# 01_Power_Suppy.net
KiCad netlist of a schematic drawn in Altium Designer
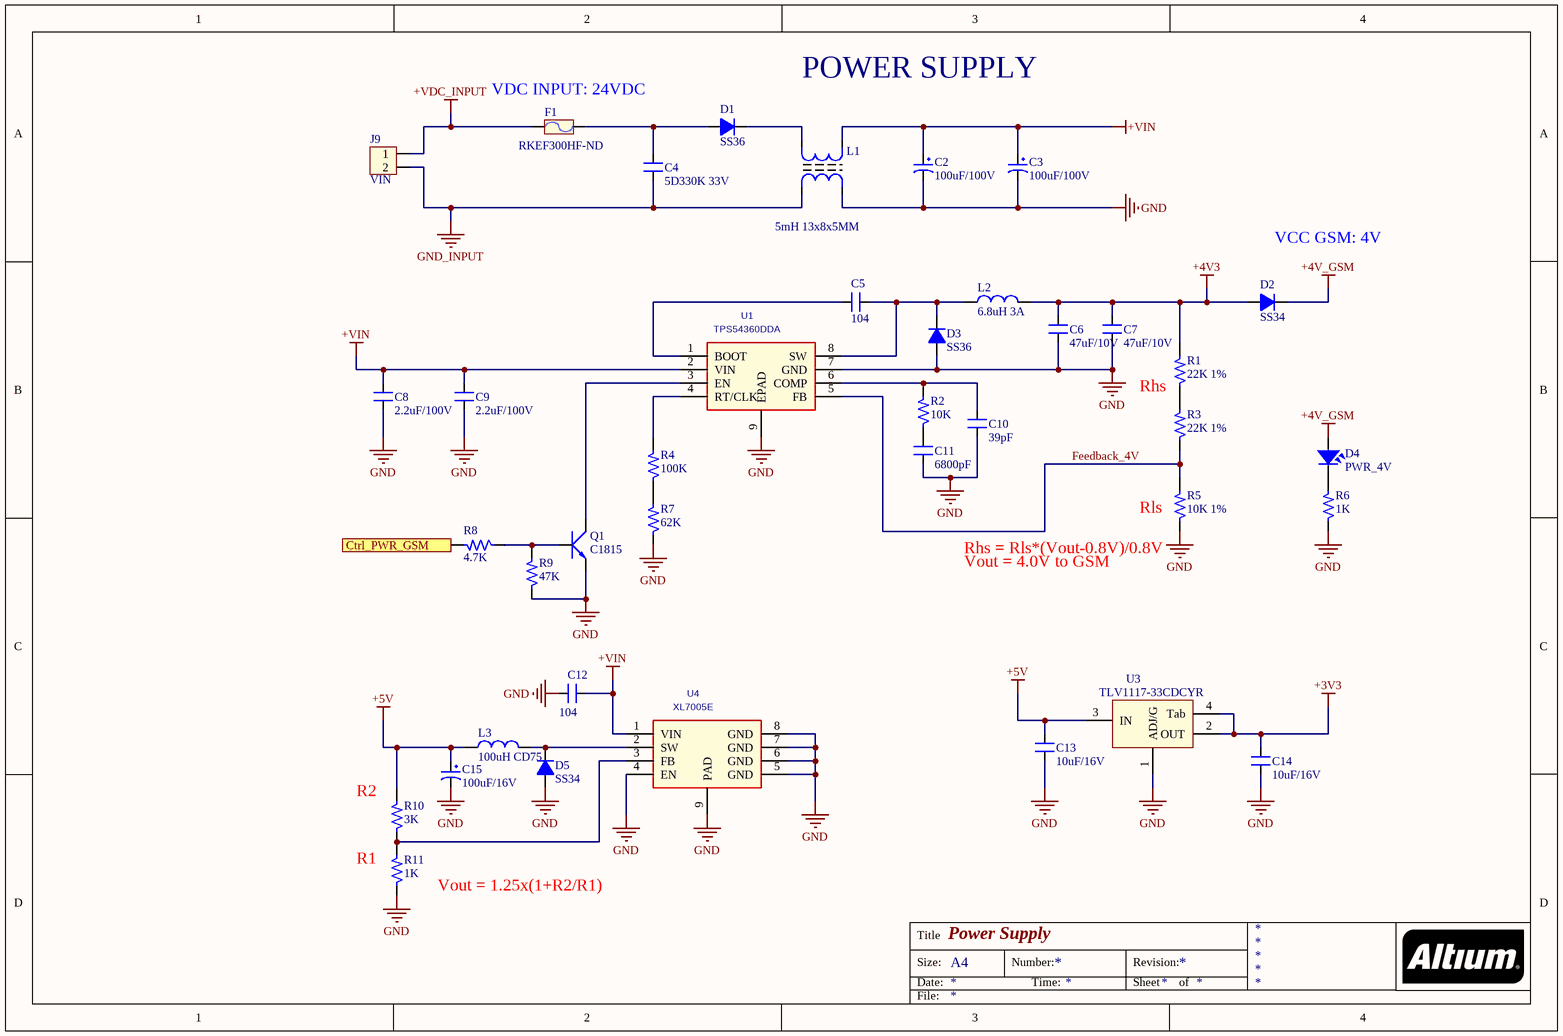
[diagram p0: [01] Power Suppy.SchDoc]

(export (version "E")
  (design (tool "Eeschema 10.0.6"))
  (components
    (comp (ref "C2")
      (value "100uF/100V")
      (footprint "CP1.5/3.4")
      (description "Cap 1000uF/16V - 220uF/50V")
      (libsource (lib "khapham") (part "CP4"))
    )
    (comp (ref "C3")
      (value "100uF/100V")
      (footprint "CP1.5/3.4")
      (description "Cap 1000uF/16V - 220uF/50V")
      (libsource (lib "khapham") (part "CP4"))
    )
    (comp (ref "C4")
      (value "5D330K 33V")
      (footprint "CN2")
      (fields (field (name "DESIGNED BY") "VanDungEvn"))
      (libsource (lib "khapham") (part "CN"))
    )
    (comp (ref "C5")
      (value "104")
      (footprint "C0603 SMT")
      (description "Cap SMD")
      (libsource (lib "khapham") (part "CM"))
    )
    (comp (ref "C6")
      (value "47uF/10V")
      (footprint "SM-1210")
      (description "CAP CER 47UF 10V X5R 1210")
      (libsource (lib "khapham") (part "CM"))
    )
    (comp (ref "C7")
      (value "47uF/10V")
      (footprint "SM-1210")
      (description "CAP CER 47UF 10V X5R 1210 1276-3380-2-ND")
      (libsource (lib "khapham") (part "CM"))
    )
    (comp (ref "C8")
      (value "2.2uF/100V")
      (footprint "SM-1210")
      (description "CAP CER 2.2UF 100V X7R 1210  445-4498-2-ND")
      (libsource (lib "khapham") (part "CM"))
    )
    (comp (ref "C9")
      (value "2.2uF/100V")
      (footprint "SM-1210")
      (description "CAP CER 2.2UF 100V X7R 1210  445-4498-2-ND")
      (libsource (lib "khapham") (part "CM"))
    )
    (comp (ref "C10")
      (value "39pF")
      (footprint "C0603 SMT")
      (description "Cap SMD")
      (libsource (lib "khapham") (part "CM"))
    )
    (comp (ref "C11")
      (value "6800pF")
      (footprint "C0603 SMT")
      (description "Cap SMD")
      (libsource (lib "khapham") (part "CM"))
    )
    (comp (ref "C12")
      (value "104")
      (footprint "C0603 SMT")
      (description "Cap SMD")
      (libsource (lib "khapham") (part "CM"))
    )
    (comp (ref "C13")
      (value "10uF/16V")
      (footprint "C0603 SMT")
      (description "Cap SMD")
      (libsource (lib "khapham") (part "CM"))
    )
    (comp (ref "C14")
      (value "10uF/16V")
      (footprint "C0603 SMT")
      (description "Cap SMD")
      (libsource (lib "khapham") (part "CM"))
    )
    (comp (ref "C15")
      (value "100uF/16V")
      (footprint "C_Alu_6.3x7.7")
      (description "Cap Aluminum, Tantalum 7343")
      (libsource (lib "khapham") (part "C-Alu-Tantalum"))
    )
    (comp (ref "D1")
      (value "SS36")
      (footprint "DO-214AB SMA")
      (description "DIODE SCHOTTKY 60V 3A SMA")
      (libsource (lib "khapham") (part "D5A"))
    )
    (comp (ref "D2")
      (value "SS34")
      (footprint "DO-214AB SMA")
      (description "DIODE SCHOTTKY 40V 3A SMC")
      (libsource (lib "khapham") (part "D1A"))
    )
    (comp (ref "D3")
      (value "SS36")
      (footprint "DO-214AB SMA")
      (description "DIODE SCHOTTKY 60V 3A SMA")
      (libsource (lib "khapham") (part "D5A"))
    )
    (comp (ref "D4")
      (value "PWR_4V")
      (footprint "Led_0603_Green")
      (description "LED 0603 RED")
      (libsource (lib "khapham") (part "LED"))
    )
    (comp (ref "D5")
      (value "SS34")
      (footprint "DO-214AB SMA")
      (description "DIODE SCHOTTKY 40V 3A SMC")
      (libsource (lib "khapham") (part "D1A"))
    )
    (comp (ref "F1")
      (value "RKEF300HF-ND")
      (footprint "FUSE2")
      (description "PTC RESET FUSE 60V 3A RADIAL")
      (fields (field (name "DESIGNED BY") "VanDungEvn"))
      (libsource (lib "khapham") (part "Fuse"))
    )
    (comp (ref "J9")
      (value "VIN")
      (footprint "Hed2V_3.96")
      (description "Header 2 (Green)")
      (libsource (lib "khapham") (part "Hed2"))
    )
    (comp (ref "L1")
      (value "5mH 13x8x5MM")
      (footprint "L2 UF9.8")
      (fields (field (name "DESIGNED BY") "VanDungEvn"))
      (libsource (lib "khapham") (part "L2x220"))
    )
    (comp (ref "L2")
      (value "6.8uH 3A")
      (footprint "L01 SMD 12*12*6")
      (description "6.8uH 3A 12x12x7MM")
      (libsource (lib "khapham") (part "L1"))
    )
    (comp (ref "L3") (value "100uH CD75") (footprint "L01 CD75") (libsource (lib "khapham") (part "L1")))
    (comp (ref "Q1")
      (value "C1815")
      (footprint "SOT23B")
      (description "NPN 600mW, ECB")
      (libsource (lib "khapham") (part "C1815"))
    )
    (comp (ref "R1")
      (value "22K 1%")
      (footprint "R0603 -SMT")
      (description "Resistor SMD")
      (libsource (lib "khapham") (part "RM"))
    )
    (comp (ref "R2")
      (value "10K")
      (footprint "R0603 -SMT")
      (description "Resistor SMD")
      (libsource (lib "khapham") (part "RM"))
    )
    (comp (ref "R3")
      (value "22K 1%")
      (footprint "R0603 -SMT")
      (description "Resistor SMD")
      (libsource (lib "khapham") (part "RM"))
    )
    (comp (ref "R4")
      (value "100K")
      (footprint "R0603 -SMT")
      (description "Resistor SMD")
      (libsource (lib "khapham") (part "RM"))
    )
    (comp (ref "R5")
      (value "10K 1%")
      (footprint "R0603 -SMT")
      (description "Resistor SMD")
      (libsource (lib "khapham") (part "RM"))
    )
    (comp (ref "R6")
      (value "1K")
      (footprint "R0603 -SMT")
      (description "Resistor SMD")
      (libsource (lib "khapham") (part "RM"))
    )
    (comp (ref "R7")
      (value "62K")
      (footprint "R0603 -SMT")
      (description "Resistor SMD")
      (libsource (lib "khapham") (part "RM"))
    )
    (comp (ref "R8")
      (value "4.7K")
      (footprint "R0603 -SMT")
      (description "Resistor SMD")
      (libsource (lib "khapham") (part "RM"))
    )
    (comp (ref "R9")
      (value "47K")
      (footprint "R0603 -SMT")
      (description "Resistor SMD")
      (libsource (lib "khapham") (part "RM"))
    )
    (comp (ref "R10")
      (value "3K")
      (footprint "R0603 -SMT")
      (description "Resistor SMD")
      (libsource (lib "khapham") (part "RM"))
    )
    (comp (ref "R11")
      (value "1K")
      (footprint "R0603 -SMT")
      (description "Resistor SMD")
      (libsource (lib "khapham") (part "RM"))
    )
    (comp (ref "U1")
      (value "TPS54360DDA")
      (footprint "DDA8_3P1X2P4-M")
      (description "REG BUCK SPLIT RAIL 8SOPWRPAD")
      (libsource (lib "khapham") (part "TPS54360DDA"))
    )
    (comp (ref "U3")
      (value "TLV1117-33CDCYR")
      (footprint "SOT223-4N")
      (description "3v3")
      (libsource (lib "khapham") (part "LM1117"))
    )
    (comp (ref "U4")
      (value "XL7005E")
      (footprint "DDA8_3P1X2P4-M")
      (description "REG BUCK SPLIT RAIL 8SOPWRPAD")
      (fields (field (name "MANUFACTURER_PART_NUMBER") "TPS54360DDA"))
      (libsource (lib "khapham") (part "XL7005"))
    )
  )
  (nets
    (net (code "1") (name "+3V3") (class "Default")
      (node (ref "C14") (pin "2") (pinfunction "2_2") (pintype "passive"))
      (node (ref "U3") (pin "2") (pinfunction "OUT_2") (pintype "passive"))
      (node (ref "U3") (pin "4") (pinfunction "Tab_4") (pintype "passive"))
    )
    (net (code "2") (name "+4V3") (class "Default")
      (node (ref "C6") (pin "2") (pinfunction "2_2") (pintype "passive"))
      (node (ref "C7") (pin "2") (pinfunction "2_2") (pintype "passive"))
      (node (ref "D2") (pin "1") (pinfunction "A_1") (pintype "passive"))
      (node (ref "L2") (pin "2") (pinfunction "2_2") (pintype "passive"))
      (node (ref "R1") (pin "2") (pinfunction "2_2") (pintype "passive"))
    )
    (net (code "3") (name "+4V_GSM") (class "Default")
      (node (ref "D2") (pin "2") (pinfunction "K_2") (pintype "passive"))
      (node (ref "D4") (pin "1") (pinfunction "1_1") (pintype "passive"))
    )
    (net (code "4") (name "+5V") (class "Default")
      (node (ref "C13") (pin "2") (pinfunction "2_2") (pintype "passive"))
      (node (ref "C15") (pin "1") (pinfunction "1_1") (pintype "passive"))
      (node (ref "L3") (pin "1") (pinfunction "1_1") (pintype "passive"))
      (node (ref "R10") (pin "2") (pinfunction "2_2") (pintype "passive"))
      (node (ref "U3") (pin "3") (pinfunction "IN_3") (pintype "passive"))
    )
    (net (code "5") (name "+VDC_INPUT") (class "Default")
      (node (ref "F1") (pin "1") (pinfunction "1_1") (pintype "passive"))
      (node (ref "J9") (pin "1") (pinfunction "1_1") (pintype "passive"))
    )
    (net (code "6") (name "+VIN") (class "Default")
      (node (ref "C12") (pin "2") (pinfunction "2_2") (pintype "passive"))
      (node (ref "C2") (pin "1") (pinfunction "1_1") (pintype "passive"))
      (node (ref "C3") (pin "1") (pinfunction "1_1") (pintype "passive"))
      (node (ref "C8") (pin "2") (pinfunction "2_2") (pintype "passive"))
      (node (ref "C9") (pin "2") (pinfunction "2_2") (pintype "passive"))
      (node (ref "L1") (pin "3") (pinfunction "3_3") (pintype "passive"))
      (node (ref "U1") (pin "2") (pinfunction "VIN_2") (pintype "passive"))
      (node (ref "U4") (pin "1") (pinfunction "VIN_1") (pintype "passive"))
    )
    (net (code "7") (name "/Ctrl_PWR_GSM") (class "Default")
      (node (ref "R8") (pin "2") (pinfunction "2_2") (pintype "passive"))
    )
    (net (code "8") (name "/Feedback_4V") (class "Default")
      (node (ref "R3") (pin "1") (pinfunction "1_1") (pintype "passive"))
      (node (ref "R5") (pin "2") (pinfunction "2_2") (pintype "passive"))
      (node (ref "U1") (pin "5") (pinfunction "FB_5") (pintype "passive"))
    )
    (net (code "9") (name "GND") (class "Default")
      (node (ref "C10") (pin "1") (pinfunction "1_1") (pintype "passive"))
      (node (ref "C11") (pin "1") (pinfunction "1_1") (pintype "passive"))
      (node (ref "C12") (pin "1") (pinfunction "1_1") (pintype "passive"))
      (node (ref "C13") (pin "1") (pinfunction "1_1") (pintype "passive"))
      (node (ref "C14") (pin "1") (pinfunction "1_1") (pintype "passive"))
      (node (ref "C15") (pin "2") (pinfunction "2_2") (pintype "passive"))
      (node (ref "C2") (pin "2") (pinfunction "2_2") (pintype "passive"))
      (node (ref "C3") (pin "2") (pinfunction "2_2") (pintype "passive"))
      (node (ref "C6") (pin "1") (pinfunction "1_1") (pintype "passive"))
      (node (ref "C7") (pin "1") (pinfunction "1_1") (pintype "passive"))
      (node (ref "C8") (pin "1") (pinfunction "1_1") (pintype "passive"))
      (node (ref "C9") (pin "1") (pinfunction "1_1") (pintype "passive"))
      (node (ref "D3") (pin "1") (pinfunction "A_1") (pintype "passive"))
      (node (ref "D5") (pin "1") (pinfunction "A_1") (pintype "passive"))
      (node (ref "L1") (pin "2") (pinfunction "2_2") (pintype "passive"))
      (node (ref "Q1") (pin "1") (pinfunction "E_1") (pintype "passive"))
      (node (ref "R11") (pin "1") (pinfunction "1_1") (pintype "passive"))
      (node (ref "R5") (pin "1") (pinfunction "1_1") (pintype "passive"))
      (node (ref "R6") (pin "1") (pinfunction "1_1") (pintype "passive"))
      (node (ref "R7") (pin "1") (pinfunction "1_1") (pintype "passive"))
      (node (ref "R9") (pin "1") (pinfunction "1_1") (pintype "passive"))
      (node (ref "U1") (pin "7") (pinfunction "GND_7") (pintype "passive"))
      (node (ref "U1") (pin "9") (pinfunction "EPAD_9") (pintype "passive"))
      (node (ref "U3") (pin "1") (pinfunction "ADJ/G_1") (pintype "passive"))
      (node (ref "U4") (pin "4") (pinfunction "EN_4") (pintype "passive"))
      (node (ref "U4") (pin "5") (pinfunction "GND_5") (pintype "passive"))
      (node (ref "U4") (pin "6") (pinfunction "GND_6") (pintype "passive"))
      (node (ref "U4") (pin "7") (pinfunction "GND_7") (pintype "passive"))
      (node (ref "U4") (pin "8") (pinfunction "GND_8") (pintype "passive"))
      (node (ref "U4") (pin "9") (pinfunction "PAD_9") (pintype "passive"))
    )
    (net (code "10") (name "GND_INPUT") (class "Default")
      (node (ref "C4") (pin "1") (pinfunction "1_1") (pintype "passive"))
      (node (ref "J9") (pin "2") (pinfunction "2_2") (pintype "passive"))
      (node (ref "L1") (pin "1") (pinfunction "1_1") (pintype "passive"))
    )
    (net (code "11") (name "Net-(C11-Pad2)") (class "Default")
      (node (ref "C11") (pin "2") (pinfunction "2_2") (pintype "passive"))
      (node (ref "R2") (pin "1") (pinfunction "1_1") (pintype "passive"))
    )
    (net (code "12") (name "Net-(D1-A)") (class "Default")
      (node (ref "C4") (pin "2") (pinfunction "2_2") (pintype "passive"))
      (node (ref "D1") (pin "1") (pinfunction "A_1") (pintype "passive"))
      (node (ref "F1") (pin "2") (pinfunction "2_2") (pintype "passive"))
    )
    (net (code "13") (name "Net-(D1-K)") (class "Default")
      (node (ref "D1") (pin "2") (pinfunction "K_2") (pintype "passive"))
      (node (ref "L1") (pin "4") (pinfunction "4_4") (pintype "passive"))
    )
    (net (code "14") (name "Net-(D3-K)") (class "Default")
      (node (ref "C5") (pin "2") (pinfunction "2_2") (pintype "passive"))
      (node (ref "D3") (pin "2") (pinfunction "K_2") (pintype "passive"))
      (node (ref "L2") (pin "1") (pinfunction "1_1") (pintype "passive"))
      (node (ref "U1") (pin "8") (pinfunction "SW_8") (pintype "passive"))
    )
    (net (code "15") (name "Net-(D4-Pad2)") (class "Default")
      (node (ref "D4") (pin "2") (pinfunction "2_2") (pintype "passive"))
      (node (ref "R6") (pin "2") (pinfunction "2_2") (pintype "passive"))
    )
    (net (code "16") (name "Net-(D5-K)") (class "Default")
      (node (ref "D5") (pin "2") (pinfunction "K_2") (pintype "passive"))
      (node (ref "L3") (pin "2") (pinfunction "2_2") (pintype "passive"))
      (node (ref "U4") (pin "2") (pinfunction "SW_2") (pintype "passive"))
    )
    (net (code "17") (name "Net-(Q1-B)") (class "Default")
      (node (ref "Q1") (pin "3") (pinfunction "B_3") (pintype "passive"))
      (node (ref "R8") (pin "1") (pinfunction "1_1") (pintype "passive"))
      (node (ref "R9") (pin "2") (pinfunction "2_2") (pintype "passive"))
    )
    (net (code "18") (name "Net-(Q1-C)") (class "Default")
      (node (ref "Q1") (pin "2") (pinfunction "C_2") (pintype "passive"))
      (node (ref "U1") (pin "3") (pinfunction "EN_3") (pintype "passive"))
    )
    (net (code "19") (name "Net-(R1-Pad1)") (class "Default")
      (node (ref "R1") (pin "1") (pinfunction "1_1") (pintype "passive"))
      (node (ref "R3") (pin "2") (pinfunction "2_2") (pintype "passive"))
    )
    (net (code "20") (name "Net-(R4-Pad1)") (class "Default")
      (node (ref "R4") (pin "1") (pinfunction "1_1") (pintype "passive"))
      (node (ref "R7") (pin "2") (pinfunction "2_2") (pintype "passive"))
    )
    (net (code "21") (name "Net-(U1-BOOT)") (class "Default")
      (node (ref "C5") (pin "1") (pinfunction "1_1") (pintype "passive"))
      (node (ref "U1") (pin "1") (pinfunction "BOOT_1") (pintype "passive"))
    )
    (net (code "22") (name "Net-(U1-COMP)") (class "Default")
      (node (ref "C10") (pin "2") (pinfunction "2_2") (pintype "passive"))
      (node (ref "R2") (pin "2") (pinfunction "2_2") (pintype "passive"))
      (node (ref "U1") (pin "6") (pinfunction "COMP_6") (pintype "passive"))
    )
    (net (code "23") (name "Net-(U1-RT{slash}CLK)") (class "Default")
      (node (ref "R4") (pin "2") (pinfunction "2_2") (pintype "passive"))
      (node (ref "U1") (pin "4") (pinfunction "RT/CLK_4") (pintype "passive"))
    )
    (net (code "24") (name "Net-(U4-FB)") (class "Default")
      (node (ref "R10") (pin "1") (pinfunction "1_1") (pintype "passive"))
      (node (ref "R11") (pin "2") (pinfunction "2_2") (pintype "passive"))
      (node (ref "U4") (pin "3") (pinfunction "FB_3") (pintype "passive"))
    )
  )
)
